# IPSv3_1.net
KiCad netlist of a schematic drawn in EAGLE
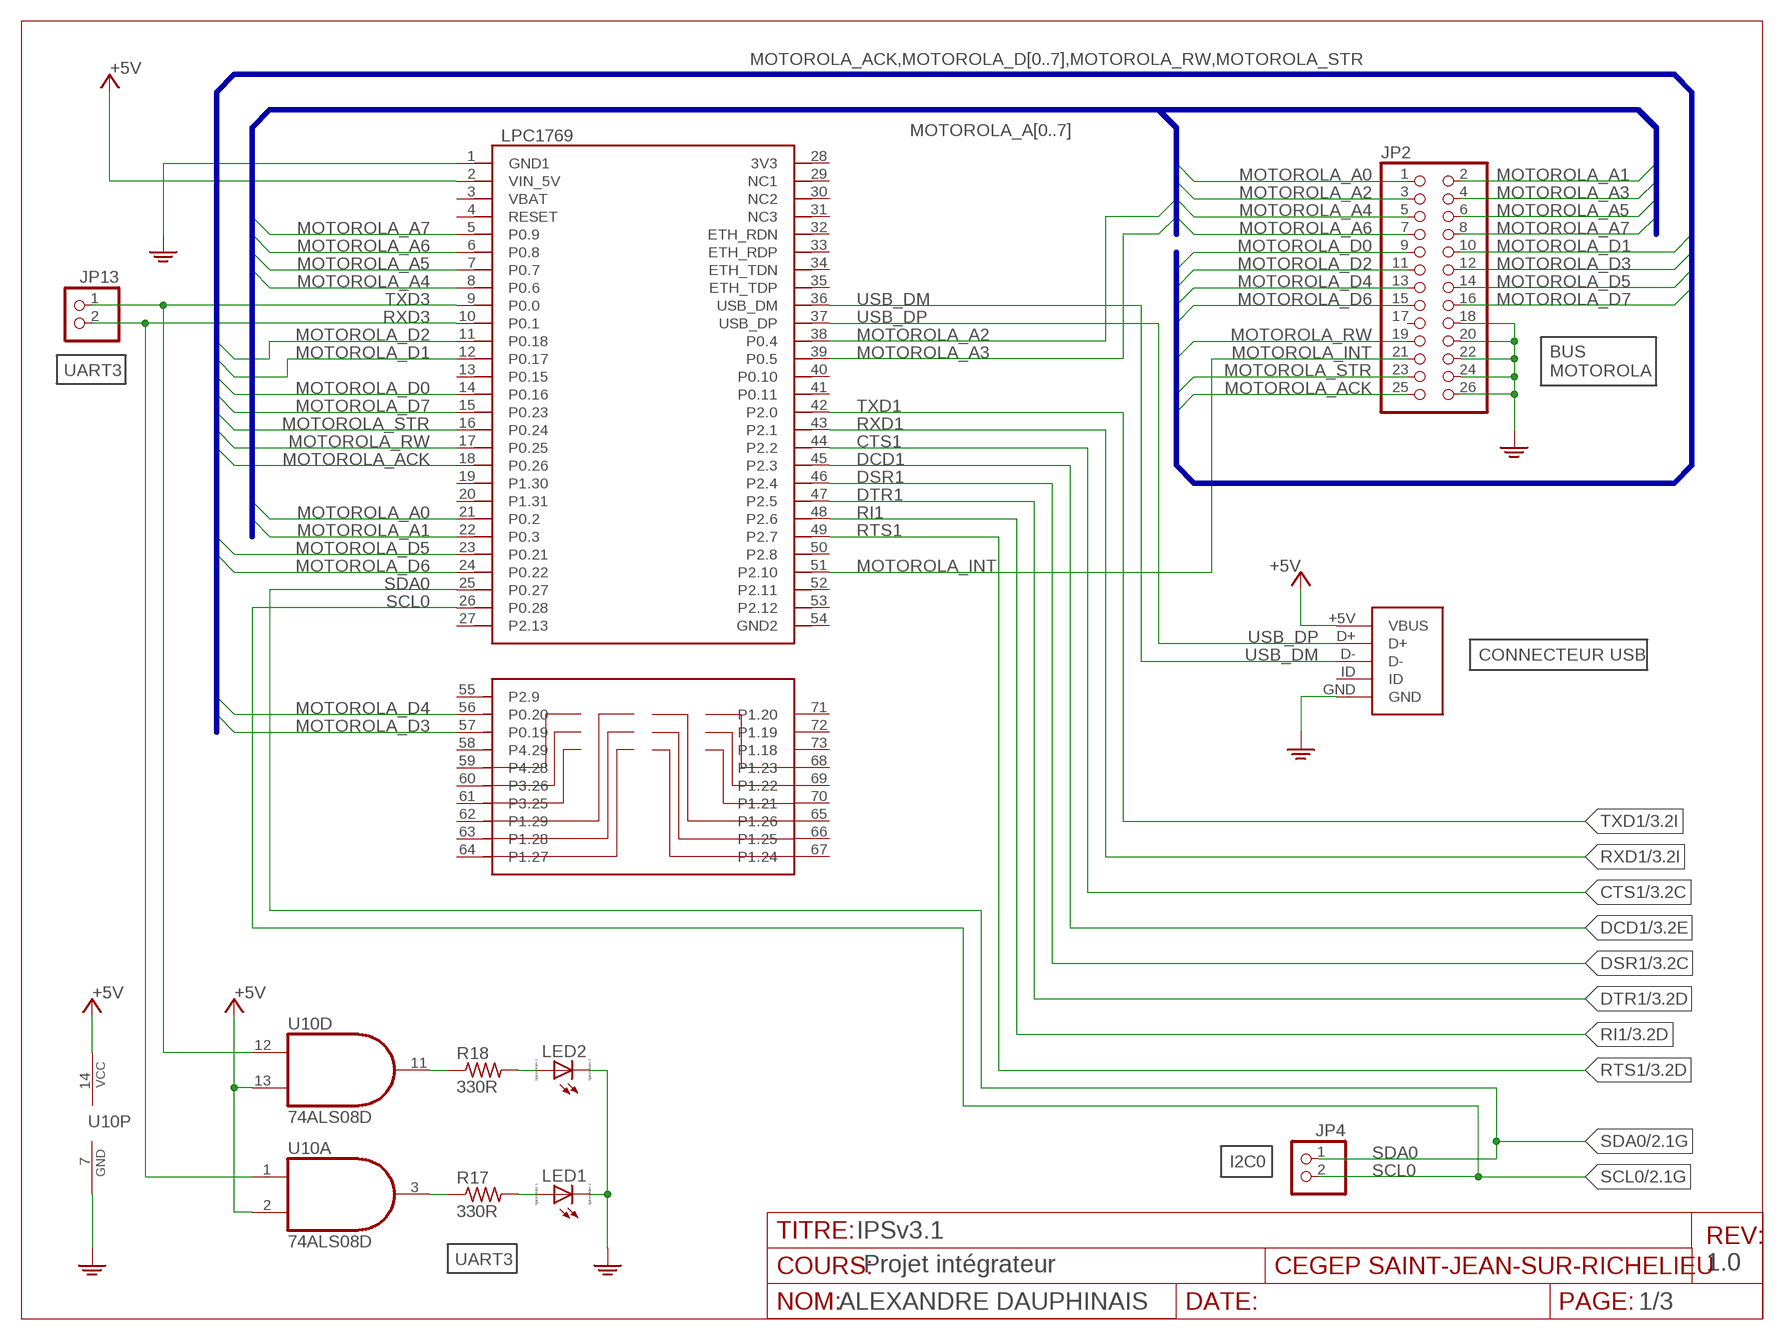
[diagram p0: schematic, sheet 1]
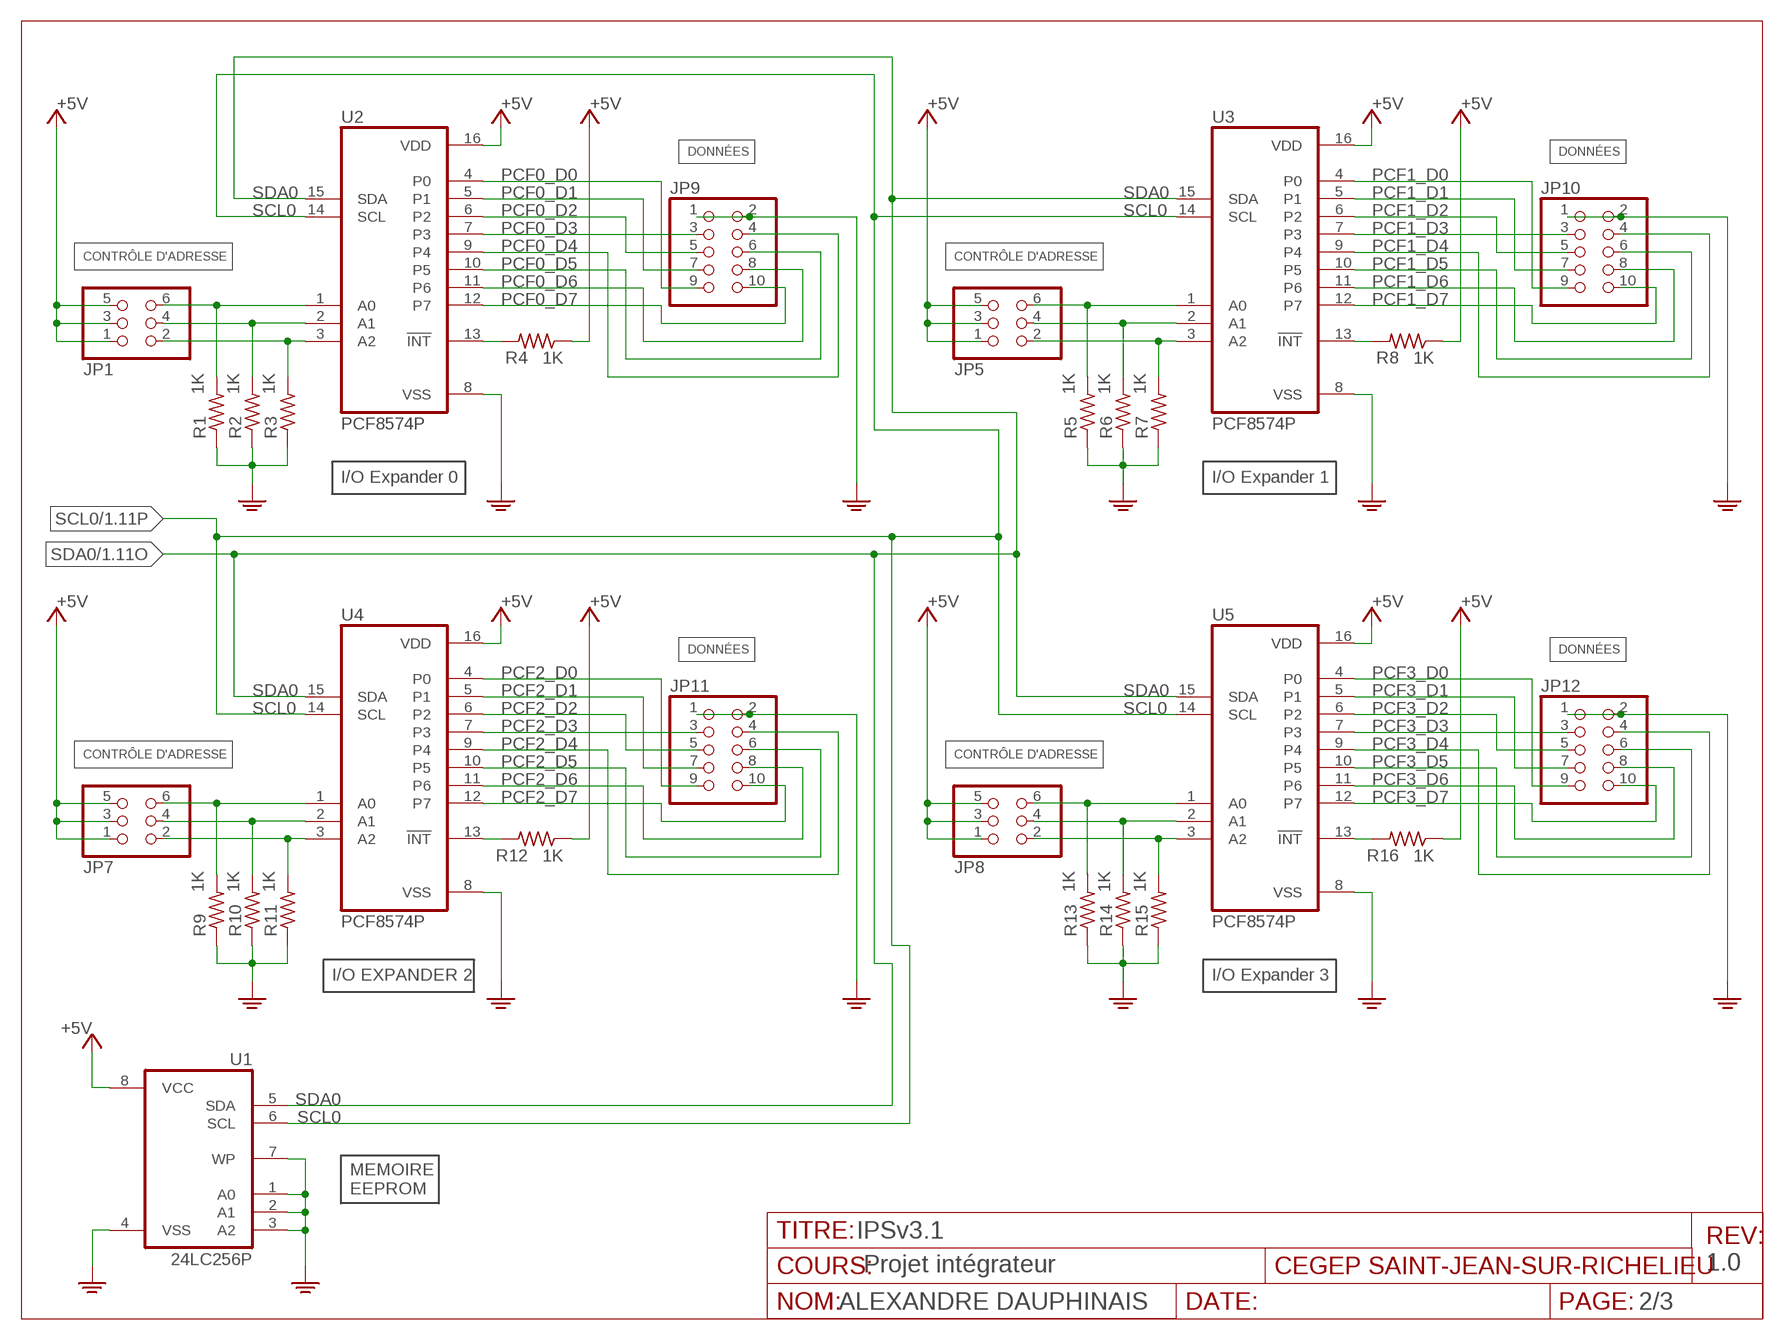
[diagram p1: schematic, sheet 2]
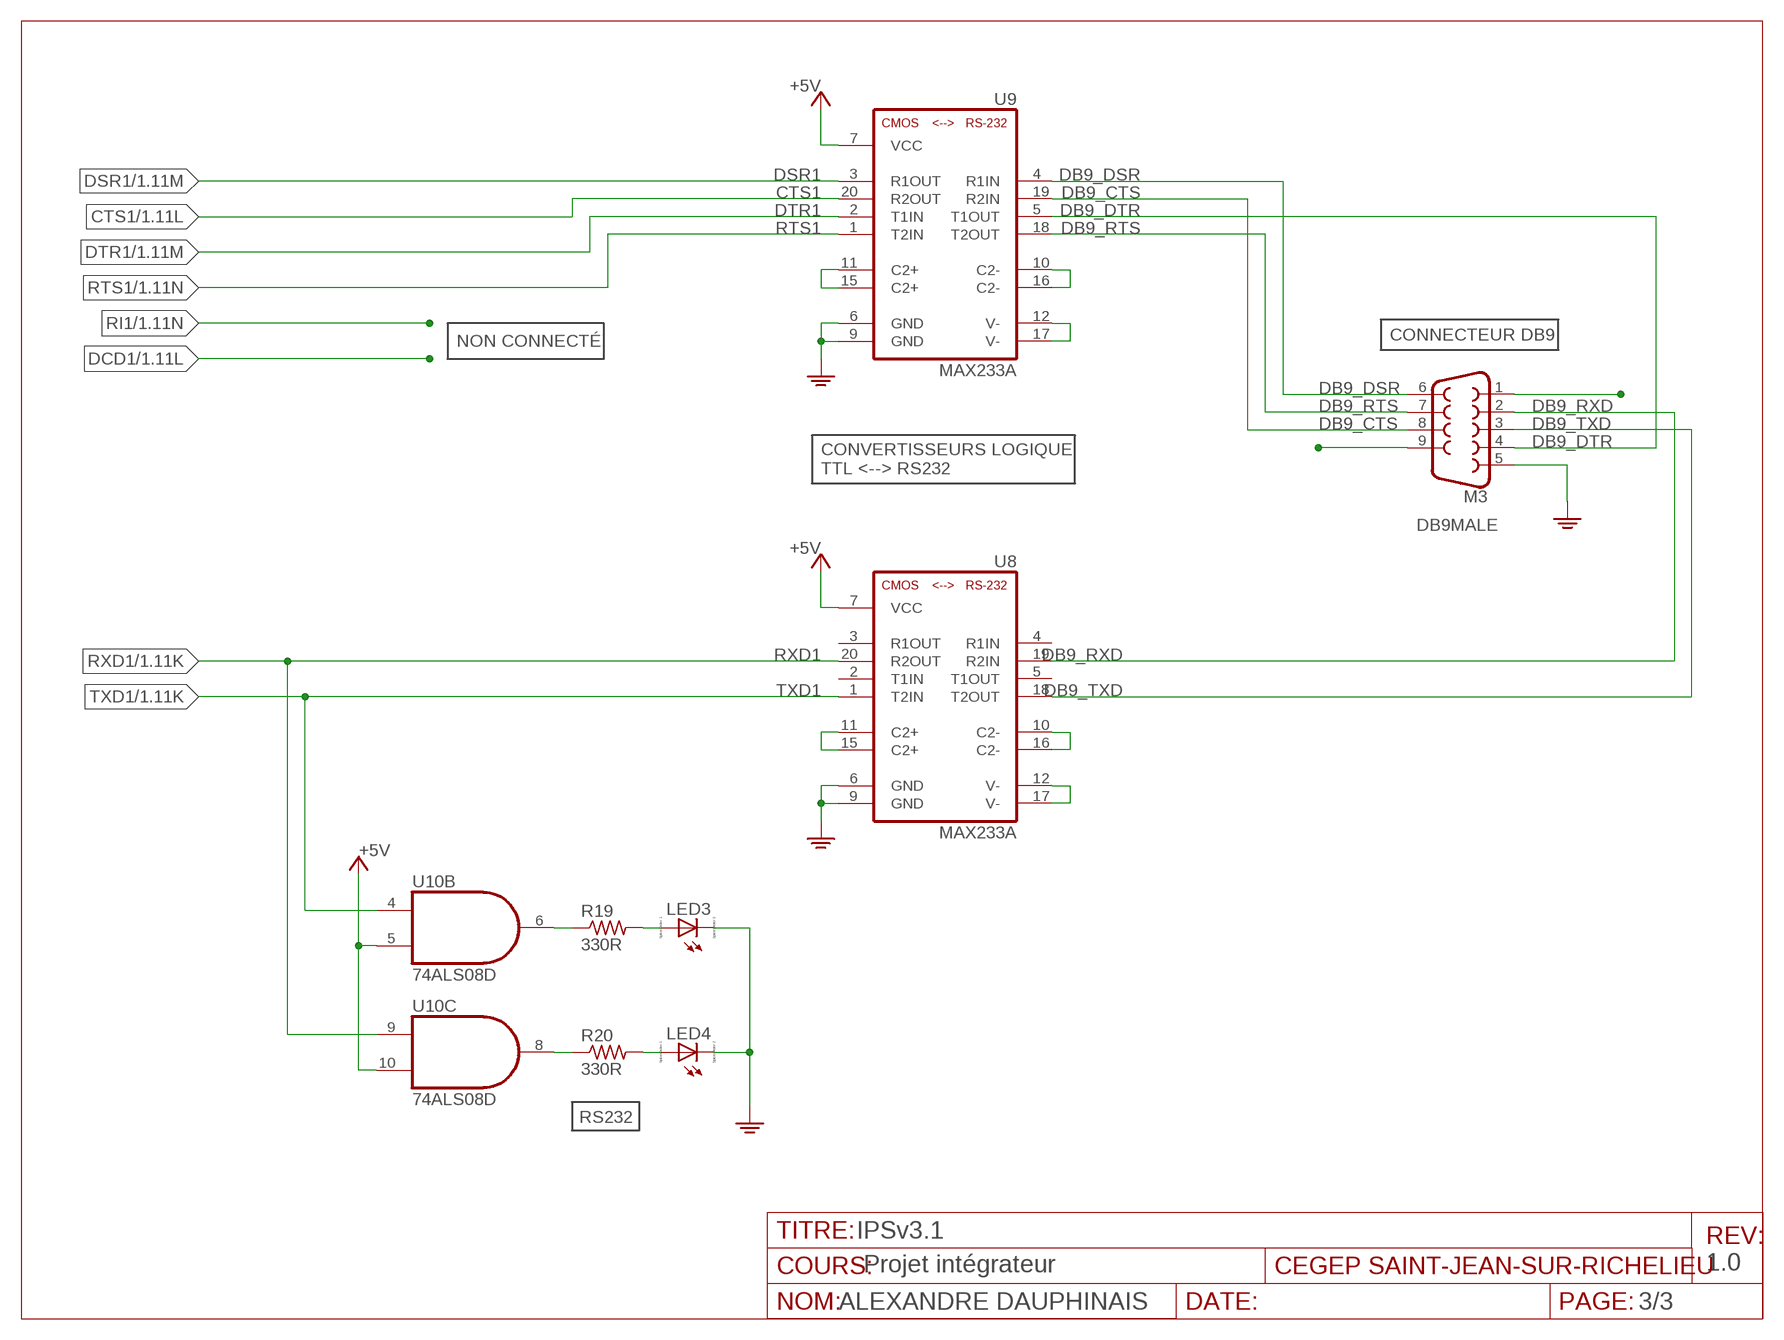
[diagram p2: schematic, sheet 3]

(export (version "E")
  (design (tool "Eeschema 10.0.6"))
  (components
    (comp (ref "LED3")
      (value "LED_JAUNE")
      (footprint "eagle-import:LED_1206")
      (libsource (lib "eagle-import") (part "LED_E"))
    )
    (comp (ref "LED4")
      (value "LED_BLEU")
      (footprint "eagle-import:LED_1206")
      (libsource (lib "eagle-import") (part "LED_E"))
    )
    (comp (ref "M3")
      (value "DB9MALE")
      (footprint "eagle-import:DB9")
      (libsource (lib "eagle-import") (part "DB9FEMALE"))
    )
    (comp (ref "R19")
      (value "330R")
      (footprint "eagle-import:R1206")
      (libsource (lib "eagle-import") (part "R-US_R1206"))
    )
    (comp (ref "R20")
      (value "330R")
      (footprint "eagle-import:R1206")
      (libsource (lib "eagle-import") (part "R-US_R1206"))
    )
    (comp (ref "U8")
      (value "MAX233A")
      (footprint "eagle-import:DIL20")
      (libsource (lib "eagle-import") (part "MAX233ACPP"))
    )
    (comp (ref "U9")
      (value "MAX233A")
      (footprint "eagle-import:DIL20")
      (libsource (lib "eagle-import") (part "MAX233ACPP"))
    )
    (comp (ref "U10")
      (value "74ALS08D")
      (footprint "eagle-import:SO14")
      (libsource (lib "eagle-import") (part "7408DALS"))
    )
    (comp (ref "JP2")
      (value "PINHD-02X13M")
      (footprint "eagle-import:02X13M")
      (libsource (lib "eagle-import") (part "PINHD-02X13M"))
    )
    (comp (ref "JP4")
      (value "PINHD-01X02M")
      (footprint "eagle-import:01X02M")
      (libsource (lib "eagle-import") (part "PINHD-01X02M"))
    )
    (comp (ref "JP13")
      (value "PINHD-01X02M")
      (footprint "eagle-import:01X02M")
      (libsource (lib "eagle-import") (part "PINHD-01X02M"))
    )
    (comp (ref "LED1")
      (value "LED_BLEU")
      (footprint "eagle-import:LED_1206")
      (libsource (lib "eagle-import") (part "LED_E"))
    )
    (comp (ref "LED2")
      (value "LED_JAUNE")
      (footprint "eagle-import:LED_1206")
      (libsource (lib "eagle-import") (part "LED_E"))
    )
    (comp (ref "M1")
      (value "LPC_LPC1769")
      (footprint "eagle-import:LPC_LPC1769")
      (libsource (lib "eagle-import") (part "LPC_LPC1769"))
    )
    (comp (ref "M2")
      (value "USB-MICRO-BREAKOUT")
      (footprint "eagle-import:USB-MICRO-BREAKOUT")
      (libsource (lib "eagle-import") (part "USB-MICRO-BREAKOUT"))
    )
    (comp (ref "R17")
      (value "330R")
      (footprint "eagle-import:R1206")
      (libsource (lib "eagle-import") (part "R-US_R1206"))
    )
    (comp (ref "R18")
      (value "330R")
      (footprint "eagle-import:R1206")
      (libsource (lib "eagle-import") (part "R-US_R1206"))
    )
    (comp (ref "JP1")
      (value "PINHD-02X03M")
      (footprint "eagle-import:02X03M")
      (libsource (lib "eagle-import") (part "PINHD-02X03M"))
    )
    (comp (ref "JP5")
      (value "PINHD-02X03M")
      (footprint "eagle-import:02X03M")
      (libsource (lib "eagle-import") (part "PINHD-02X03M"))
    )
    (comp (ref "JP7")
      (value "PINHD-02X03M")
      (footprint "eagle-import:02X03M")
      (libsource (lib "eagle-import") (part "PINHD-02X03M"))
    )
    (comp (ref "JP8")
      (value "PINHD-02X03M")
      (footprint "eagle-import:02X03M")
      (libsource (lib "eagle-import") (part "PINHD-02X03M"))
    )
    (comp (ref "JP9")
      (value "PINHD-02X05M")
      (footprint "eagle-import:02X05M")
      (libsource (lib "eagle-import") (part "PINHD-02X05M"))
    )
    (comp (ref "JP10")
      (value "PINHD-02X05M")
      (footprint "eagle-import:02X05M")
      (libsource (lib "eagle-import") (part "PINHD-02X05M"))
    )
    (comp (ref "JP11")
      (value "PINHD-02X05M")
      (footprint "eagle-import:02X05M")
      (libsource (lib "eagle-import") (part "PINHD-02X05M"))
    )
    (comp (ref "JP12")
      (value "PINHD-02X05M")
      (footprint "eagle-import:02X05M")
      (libsource (lib "eagle-import") (part "PINHD-02X05M"))
    )
    (comp (ref "R1")
      (value "1K")
      (footprint "eagle-import:R1206")
      (libsource (lib "eagle-import") (part "R-US_R1206"))
    )
    (comp (ref "R2")
      (value "1K")
      (footprint "eagle-import:R1206")
      (libsource (lib "eagle-import") (part "R-US_R1206"))
    )
    (comp (ref "R3")
      (value "1K")
      (footprint "eagle-import:R1206")
      (libsource (lib "eagle-import") (part "R-US_R1206"))
    )
    (comp (ref "R4")
      (value "1K")
      (footprint "eagle-import:R1206")
      (libsource (lib "eagle-import") (part "R-US_R1206"))
    )
    (comp (ref "R5")
      (value "1K")
      (footprint "eagle-import:R1206")
      (libsource (lib "eagle-import") (part "R-US_R1206"))
    )
    (comp (ref "R6")
      (value "1K")
      (footprint "eagle-import:R1206")
      (libsource (lib "eagle-import") (part "R-US_R1206"))
    )
    (comp (ref "R7")
      (value "1K")
      (footprint "eagle-import:R1206")
      (libsource (lib "eagle-import") (part "R-US_R1206"))
    )
    (comp (ref "R8")
      (value "1K")
      (footprint "eagle-import:R1206")
      (libsource (lib "eagle-import") (part "R-US_R1206"))
    )
    (comp (ref "R9")
      (value "1K")
      (footprint "eagle-import:R1206")
      (libsource (lib "eagle-import") (part "R-US_R1206"))
    )
    (comp (ref "R10")
      (value "1K")
      (footprint "eagle-import:R1206")
      (libsource (lib "eagle-import") (part "R-US_R1206"))
    )
    (comp (ref "R11")
      (value "1K")
      (footprint "eagle-import:R1206")
      (libsource (lib "eagle-import") (part "R-US_R1206"))
    )
    (comp (ref "R12")
      (value "1K")
      (footprint "eagle-import:R1206")
      (libsource (lib "eagle-import") (part "R-US_R1206"))
    )
    (comp (ref "R13")
      (value "1K")
      (footprint "eagle-import:R1206")
      (libsource (lib "eagle-import") (part "R-US_R1206"))
    )
    (comp (ref "R14")
      (value "1K")
      (footprint "eagle-import:R1206")
      (libsource (lib "eagle-import") (part "R-US_R1206"))
    )
    (comp (ref "R15")
      (value "1K")
      (footprint "eagle-import:R1206")
      (libsource (lib "eagle-import") (part "R-US_R1206"))
    )
    (comp (ref "R16")
      (value "1K")
      (footprint "eagle-import:R1206")
      (libsource (lib "eagle-import") (part "R-US_R1206"))
    )
    (comp (ref "U1")
      (value "24LC256P")
      (footprint "eagle-import:DIL08")
      (libsource (lib "eagle-import") (part "24LC256P"))
    )
    (comp (ref "U2")
      (value "PCF8574P")
      (footprint "eagle-import:DIL16")
      (libsource (lib "eagle-import") (part "PCF8574P"))
    )
    (comp (ref "U3")
      (value "PCF8574P")
      (footprint "eagle-import:DIL16")
      (libsource (lib "eagle-import") (part "PCF8574P"))
    )
    (comp (ref "U4")
      (value "PCF8574P")
      (footprint "eagle-import:DIL16")
      (libsource (lib "eagle-import") (part "PCF8574P"))
    )
    (comp (ref "U5")
      (value "PCF8574P")
      (footprint "eagle-import:DIL16")
      (libsource (lib "eagle-import") (part "PCF8574P"))
    )
  )
  (nets
    (net (code "1") (name "+5V") (class "Default")
      (node (ref "JP1") (pin "1") (pinfunction "1_1") (pintype "passive"))
      (node (ref "JP1") (pin "3") (pinfunction "3_3") (pintype "passive"))
      (node (ref "JP1") (pin "5") (pinfunction "5_5") (pintype "passive"))
      (node (ref "JP5") (pin "1") (pinfunction "1_1") (pintype "passive"))
      (node (ref "JP5") (pin "3") (pinfunction "3_3") (pintype "passive"))
      (node (ref "JP5") (pin "5") (pinfunction "5_5") (pintype "passive"))
      (node (ref "JP7") (pin "1") (pinfunction "1_1") (pintype "passive"))
      (node (ref "JP7") (pin "3") (pinfunction "3_3") (pintype "passive"))
      (node (ref "JP7") (pin "5") (pinfunction "5_5") (pintype "passive"))
      (node (ref "JP8") (pin "1") (pinfunction "1_1") (pintype "passive"))
      (node (ref "JP8") (pin "3") (pinfunction "3_3") (pintype "passive"))
      (node (ref "JP8") (pin "5") (pinfunction "5_5") (pintype "passive"))
      (node (ref "M1") (pin "2") (pinfunction "VIN_5V_2") (pintype "bidirectional"))
      (node (ref "M2") (pin "+5V") (pinfunction "VBUS_+5V") (pintype "power_in"))
      (node (ref "R12") (pin "1") (pinfunction "1_1") (pintype "passive"))
      (node (ref "R16") (pin "1") (pinfunction "1_1") (pintype "passive"))
      (node (ref "R4") (pin "1") (pinfunction "1_1") (pintype "passive"))
      (node (ref "R8") (pin "1") (pinfunction "1_1") (pintype "passive"))
      (node (ref "U1") (pin "8") (pinfunction "VCC_8") (pintype "power_in"))
      (node (ref "U10") (pin "10") (pinfunction "I1_10") (pintype "input"))
      (node (ref "U10") (pin "13") (pinfunction "I1_13") (pintype "input"))
      (node (ref "U10") (pin "14") (pinfunction "VCC_14") (pintype "power_in"))
      (node (ref "U10") (pin "2") (pinfunction "I1_2") (pintype "input"))
      (node (ref "U10") (pin "5") (pinfunction "I1_5") (pintype "input"))
      (node (ref "U2") (pin "16") (pinfunction "VDD_16") (pintype "power_in"))
      (node (ref "U3") (pin "16") (pinfunction "VDD_16") (pintype "power_in"))
      (node (ref "U4") (pin "16") (pinfunction "VDD_16") (pintype "power_in"))
      (node (ref "U5") (pin "16") (pinfunction "VDD_16") (pintype "power_in"))
      (node (ref "U8") (pin "7") (pinfunction "VCC_7") (pintype "power_in"))
      (node (ref "U9") (pin "7") (pinfunction "VCC_7") (pintype "power_in"))
    )
    (net (code "4") (name "CTS1") (class "Default")
      (node (ref "M1") (pin "44") (pinfunction "P2.2_44") (pintype "bidirectional"))
      (node (ref "U9") (pin "20") (pinfunction "R2OUT_20") (pintype "output"))
    )
    (net (code "5") (name "DB9_CTS") (class "Default")
      (node (ref "M3") (pin "8") (pinfunction "8_8") (pintype "passive"))
      (node (ref "U9") (pin "19") (pinfunction "R2IN_19") (pintype "input"))
    )
    (net (code "6") (name "DB9_DSR") (class "Default")
      (node (ref "M3") (pin "6") (pinfunction "6_6") (pintype "passive"))
      (node (ref "U9") (pin "4") (pinfunction "R1IN_4") (pintype "input"))
    )
    (net (code "7") (name "DB9_DTR") (class "Default")
      (node (ref "M3") (pin "4") (pinfunction "4_4") (pintype "passive"))
      (node (ref "U9") (pin "5") (pinfunction "T1OUT_5") (pintype "output"))
    )
    (net (code "8") (name "DB9_RTS") (class "Default")
      (node (ref "M3") (pin "7") (pinfunction "7_7") (pintype "passive"))
      (node (ref "U9") (pin "18") (pinfunction "T2OUT_18") (pintype "output"))
    )
    (net (code "9") (name "DB9_RXD") (class "Default")
      (node (ref "M3") (pin "2") (pinfunction "2_2") (pintype "passive"))
      (node (ref "U8") (pin "19") (pinfunction "R2IN_19") (pintype "input"))
    )
    (net (code "10") (name "DB9_TXD") (class "Default")
      (node (ref "M3") (pin "3") (pinfunction "3_3") (pintype "passive"))
      (node (ref "U8") (pin "18") (pinfunction "T2OUT_18") (pintype "output"))
    )
    (net (code "11") (name "DCD1") (class "Default")
      (node (ref "M1") (pin "45") (pinfunction "P2.3_45") (pintype "bidirectional"))
    )
    (net (code "12") (name "DSR1") (class "Default")
      (node (ref "M1") (pin "46") (pinfunction "P2.4_46") (pintype "bidirectional"))
      (node (ref "U9") (pin "3") (pinfunction "R1OUT_3") (pintype "output"))
    )
    (net (code "13") (name "DTR1") (class "Default")
      (node (ref "M1") (pin "47") (pinfunction "P2.5_47") (pintype "bidirectional"))
      (node (ref "U9") (pin "2") (pinfunction "T1IN_2") (pintype "input"))
    )
    (net (code "14") (name "GND") (class "Default")
      (node (ref "JP10") (pin "1") (pinfunction "1_1") (pintype "passive"))
      (node (ref "JP10") (pin "2") (pinfunction "2_2") (pintype "passive"))
      (node (ref "JP11") (pin "1") (pinfunction "1_1") (pintype "passive"))
      (node (ref "JP11") (pin "2") (pinfunction "2_2") (pintype "passive"))
      (node (ref "JP12") (pin "1") (pinfunction "1_1") (pintype "passive"))
      (node (ref "JP12") (pin "2") (pinfunction "2_2") (pintype "passive"))
      (node (ref "JP2") (pin "18") (pinfunction "18_18") (pintype "passive"))
      (node (ref "JP2") (pin "20") (pinfunction "20_20") (pintype "passive"))
      (node (ref "JP2") (pin "22") (pinfunction "22_22") (pintype "passive"))
      (node (ref "JP2") (pin "24") (pinfunction "24_24") (pintype "passive"))
      (node (ref "JP2") (pin "26") (pinfunction "26_26") (pintype "passive"))
      (node (ref "JP9") (pin "1") (pinfunction "1_1") (pintype "passive"))
      (node (ref "JP9") (pin "2") (pinfunction "2_2") (pintype "passive"))
      (node (ref "LED1") (pin "C") (pinfunction "C_C") (pintype "passive"))
      (node (ref "LED2") (pin "C") (pinfunction "C_C") (pintype "passive"))
      (node (ref "LED3") (pin "C") (pinfunction "C_C") (pintype "passive"))
      (node (ref "LED4") (pin "C") (pinfunction "C_C") (pintype "passive"))
      (node (ref "M1") (pin "1") (pinfunction "GND1_1") (pintype "bidirectional"))
      (node (ref "M2") (pin "GND") (pinfunction "GND_GND") (pintype "power_in"))
      (node (ref "M3") (pin "5") (pinfunction "5_5") (pintype "passive"))
      (node (ref "R1") (pin "1") (pinfunction "1_1") (pintype "passive"))
      (node (ref "R10") (pin "1") (pinfunction "1_1") (pintype "passive"))
      (node (ref "R11") (pin "1") (pinfunction "1_1") (pintype "passive"))
      (node (ref "R13") (pin "1") (pinfunction "1_1") (pintype "passive"))
      (node (ref "R14") (pin "1") (pinfunction "1_1") (pintype "passive"))
      (node (ref "R15") (pin "1") (pinfunction "1_1") (pintype "passive"))
      (node (ref "R2") (pin "1") (pinfunction "1_1") (pintype "passive"))
      (node (ref "R3") (pin "1") (pinfunction "1_1") (pintype "passive"))
      (node (ref "R5") (pin "1") (pinfunction "1_1") (pintype "passive"))
      (node (ref "R6") (pin "1") (pinfunction "1_1") (pintype "passive"))
      (node (ref "R7") (pin "1") (pinfunction "1_1") (pintype "passive"))
      (node (ref "R9") (pin "1") (pinfunction "1_1") (pintype "passive"))
      (node (ref "U1") (pin "1") (pinfunction "A0_1") (pintype "input"))
      (node (ref "U1") (pin "2") (pinfunction "A1_2") (pintype "input"))
      (node (ref "U1") (pin "3") (pinfunction "A2_3") (pintype "input"))
      (node (ref "U1") (pin "4") (pinfunction "VSS_4") (pintype "power_in"))
      (node (ref "U1") (pin "7") (pinfunction "WP_7") (pintype "input"))
      (node (ref "U10") (pin "7") (pinfunction "GND_7") (pintype "power_in"))
      (node (ref "U2") (pin "8") (pinfunction "VSS_8") (pintype "power_in"))
      (node (ref "U3") (pin "8") (pinfunction "VSS_8") (pintype "power_in"))
      (node (ref "U4") (pin "8") (pinfunction "VSS_8") (pintype "power_in"))
      (node (ref "U5") (pin "8") (pinfunction "VSS_8") (pintype "power_in"))
      (node (ref "U8") (pin "6") (pinfunction "GND_6") (pintype "power_in"))
      (node (ref "U8") (pin "9") (pinfunction "GND_9") (pintype "power_in"))
      (node (ref "U9") (pin "6") (pinfunction "GND_6") (pintype "power_in"))
      (node (ref "U9") (pin "9") (pinfunction "GND_9") (pintype "power_in"))
    )
    (net (code "15") (name "MOTOROLA_A0") (class "Default")
      (node (ref "JP2") (pin "1") (pinfunction "1_1") (pintype "passive"))
      (node (ref "M1") (pin "21") (pinfunction "P0.2_21") (pintype "bidirectional"))
    )
    (net (code "16") (name "MOTOROLA_A1") (class "Default")
      (node (ref "JP2") (pin "2") (pinfunction "2_2") (pintype "passive"))
      (node (ref "M1") (pin "22") (pinfunction "P0.3_22") (pintype "bidirectional"))
    )
    (net (code "17") (name "MOTOROLA_A2") (class "Default")
      (node (ref "JP2") (pin "3") (pinfunction "3_3") (pintype "passive"))
      (node (ref "M1") (pin "38") (pinfunction "P0.4_38") (pintype "bidirectional"))
    )
    (net (code "18") (name "MOTOROLA_A3") (class "Default")
      (node (ref "JP2") (pin "4") (pinfunction "4_4") (pintype "passive"))
      (node (ref "M1") (pin "39") (pinfunction "P0.5_39") (pintype "bidirectional"))
    )
    (net (code "19") (name "MOTOROLA_A4") (class "Default")
      (node (ref "JP2") (pin "5") (pinfunction "5_5") (pintype "passive"))
      (node (ref "M1") (pin "8") (pinfunction "P0.6_8") (pintype "bidirectional"))
    )
    (net (code "20") (name "MOTOROLA_A5") (class "Default")
      (node (ref "JP2") (pin "6") (pinfunction "6_6") (pintype "passive"))
      (node (ref "M1") (pin "7") (pinfunction "P0.7_7") (pintype "bidirectional"))
    )
    (net (code "21") (name "MOTOROLA_A6") (class "Default")
      (node (ref "JP2") (pin "7") (pinfunction "7_7") (pintype "passive"))
      (node (ref "M1") (pin "6") (pinfunction "P0.8_6") (pintype "bidirectional"))
    )
    (net (code "22") (name "MOTOROLA_A7") (class "Default")
      (node (ref "JP2") (pin "8") (pinfunction "8_8") (pintype "passive"))
      (node (ref "M1") (pin "5") (pinfunction "P0.9_5") (pintype "bidirectional"))
    )
    (net (code "23") (name "MOTOROLA_ACK") (class "Default")
      (node (ref "JP2") (pin "25") (pinfunction "25_25") (pintype "passive"))
      (node (ref "M1") (pin "18") (pinfunction "P0.26_18") (pintype "bidirectional"))
    )
    (net (code "24") (name "MOTOROLA_D0") (class "Default")
      (node (ref "JP2") (pin "9") (pinfunction "9_9") (pintype "passive"))
      (node (ref "M1") (pin "14") (pinfunction "P0.16_14") (pintype "bidirectional"))
    )
    (net (code "25") (name "MOTOROLA_D1") (class "Default")
      (node (ref "JP2") (pin "10") (pinfunction "10_10") (pintype "passive"))
      (node (ref "M1") (pin "12") (pinfunction "P0.17_12") (pintype "bidirectional"))
    )
    (net (code "26") (name "MOTOROLA_D2") (class "Default")
      (node (ref "JP2") (pin "11") (pinfunction "11_11") (pintype "passive"))
      (node (ref "M1") (pin "11") (pinfunction "P0.18_11") (pintype "bidirectional"))
    )
    (net (code "27") (name "MOTOROLA_D3") (class "Default")
      (node (ref "JP2") (pin "12") (pinfunction "12_12") (pintype "passive"))
      (node (ref "M1") (pin "57") (pinfunction "P0.19_57") (pintype "bidirectional"))
    )
    (net (code "28") (name "MOTOROLA_D4") (class "Default")
      (node (ref "JP2") (pin "13") (pinfunction "13_13") (pintype "passive"))
      (node (ref "M1") (pin "56") (pinfunction "P0.20_56") (pintype "bidirectional"))
    )
    (net (code "29") (name "MOTOROLA_D5") (class "Default")
      (node (ref "JP2") (pin "14") (pinfunction "14_14") (pintype "passive"))
      (node (ref "M1") (pin "23") (pinfunction "P0.21_23") (pintype "bidirectional"))
    )
    (net (code "30") (name "MOTOROLA_D6") (class "Default")
      (node (ref "JP2") (pin "15") (pinfunction "15_15") (pintype "passive"))
      (node (ref "M1") (pin "24") (pinfunction "P0.22_24") (pintype "bidirectional"))
    )
    (net (code "31") (name "MOTOROLA_D7") (class "Default")
      (node (ref "JP2") (pin "16") (pinfunction "16_16") (pintype "passive"))
      (node (ref "M1") (pin "15") (pinfunction "P0.23_15") (pintype "bidirectional"))
    )
    (net (code "32") (name "MOTOROLA_INT") (class "Default")
      (node (ref "JP2") (pin "21") (pinfunction "21_21") (pintype "passive"))
      (node (ref "M1") (pin "51") (pinfunction "P2.10_51") (pintype "bidirectional"))
    )
    (net (code "33") (name "MOTOROLA_RW") (class "Default")
      (node (ref "JP2") (pin "19") (pinfunction "19_19") (pintype "passive"))
      (node (ref "M1") (pin "17") (pinfunction "P0.25_17") (pintype "bidirectional"))
    )
    (net (code "34") (name "MOTOROLA_STR") (class "Default")
      (node (ref "JP2") (pin "23") (pinfunction "23_23") (pintype "passive"))
      (node (ref "M1") (pin "16") (pinfunction "P0.24_16") (pintype "bidirectional"))
    )
    (net (code "35") (name "Net-(LED1-PadA)") (class "Default")
      (node (ref "LED1") (pin "A") (pinfunction "A_A") (pintype "passive"))
      (node (ref "R17") (pin "2") (pinfunction "2_2") (pintype "passive"))
    )
    (net (code "36") (name "Net-(LED2-PadA)") (class "Default")
      (node (ref "LED2") (pin "A") (pinfunction "A_A") (pintype "passive"))
      (node (ref "R18") (pin "2") (pinfunction "2_2") (pintype "passive"))
    )
    (net (code "37") (name "Net-(LED3-PadA)") (class "Default")
      (node (ref "LED3") (pin "A") (pinfunction "A_A") (pintype "passive"))
      (node (ref "R19") (pin "2") (pinfunction "2_2") (pintype "passive"))
    )
    (net (code "38") (name "Net-(LED4-PadA)") (class "Default")
      (node (ref "LED4") (pin "A") (pinfunction "A_A") (pintype "passive"))
      (node (ref "R20") (pin "2") (pinfunction "2_2") (pintype "passive"))
    )
    (net (code "39") (name "Net-(U2-A0)") (class "Default")
      (node (ref "JP1") (pin "6") (pinfunction "6_6") (pintype "passive"))
      (node (ref "R1") (pin "2") (pinfunction "2_2") (pintype "passive"))
      (node (ref "U2") (pin "1") (pinfunction "A0_1") (pintype "input"))
    )
    (net (code "40") (name "Net-(U2-A1)") (class "Default")
      (node (ref "JP1") (pin "4") (pinfunction "4_4") (pintype "passive"))
      (node (ref "R2") (pin "2") (pinfunction "2_2") (pintype "passive"))
      (node (ref "U2") (pin "2") (pinfunction "A1_2") (pintype "input"))
    )
    (net (code "41") (name "Net-(U2-A2)") (class "Default")
      (node (ref "JP1") (pin "2") (pinfunction "2_2") (pintype "passive"))
      (node (ref "R3") (pin "2") (pinfunction "2_2") (pintype "passive"))
      (node (ref "U2") (pin "3") (pinfunction "A2_3") (pintype "input"))
    )
    (net (code "42") (name "Net-(U2-~{INT})") (class "Default")
      (node (ref "R4") (pin "2") (pinfunction "2_2") (pintype "passive"))
      (node (ref "U2") (pin "13") (pinfunction "~{INT}_13") (pintype "output"))
    )
    (net (code "43") (name "Net-(U3-A0)") (class "Default")
      (node (ref "JP5") (pin "6") (pinfunction "6_6") (pintype "passive"))
      (node (ref "R5") (pin "2") (pinfunction "2_2") (pintype "passive"))
      (node (ref "U3") (pin "1") (pinfunction "A0_1") (pintype "input"))
    )
    (net (code "44") (name "Net-(U3-A1)") (class "Default")
      (node (ref "JP5") (pin "4") (pinfunction "4_4") (pintype "passive"))
      (node (ref "R6") (pin "2") (pinfunction "2_2") (pintype "passive"))
      (node (ref "U3") (pin "2") (pinfunction "A1_2") (pintype "input"))
    )
    (net (code "45") (name "Net-(U3-A2)") (class "Default")
      (node (ref "JP5") (pin "2") (pinfunction "2_2") (pintype "passive"))
      (node (ref "R7") (pin "2") (pinfunction "2_2") (pintype "passive"))
      (node (ref "U3") (pin "3") (pinfunction "A2_3") (pintype "input"))
    )
    (net (code "46") (name "Net-(U3-~{INT})") (class "Default")
      (node (ref "R8") (pin "2") (pinfunction "2_2") (pintype "passive"))
      (node (ref "U3") (pin "13") (pinfunction "~{INT}_13") (pintype "output"))
    )
    (net (code "47") (name "Net-(U4-A0)") (class "Default")
      (node (ref "JP7") (pin "6") (pinfunction "6_6") (pintype "passive"))
      (node (ref "R9") (pin "2") (pinfunction "2_2") (pintype "passive"))
      (node (ref "U4") (pin "1") (pinfunction "A0_1") (pintype "input"))
    )
    (net (code "48") (name "Net-(U4-A1)") (class "Default")
      (node (ref "JP7") (pin "4") (pinfunction "4_4") (pintype "passive"))
      (node (ref "R10") (pin "2") (pinfunction "2_2") (pintype "passive"))
      (node (ref "U4") (pin "2") (pinfunction "A1_2") (pintype "input"))
    )
    (net (code "49") (name "Net-(U4-A2)") (class "Default")
      (node (ref "JP7") (pin "2") (pinfunction "2_2") (pintype "passive"))
      (node (ref "R11") (pin "2") (pinfunction "2_2") (pintype "passive"))
      (node (ref "U4") (pin "3") (pinfunction "A2_3") (pintype "input"))
    )
    (net (code "50") (name "Net-(U4-~{INT})") (class "Default")
      (node (ref "R12") (pin "2") (pinfunction "2_2") (pintype "passive"))
      (node (ref "U4") (pin "13") (pinfunction "~{INT}_13") (pintype "output"))
    )
    (net (code "51") (name "Net-(U5-A0)") (class "Default")
      (node (ref "JP8") (pin "6") (pinfunction "6_6") (pintype "passive"))
      (node (ref "R13") (pin "2") (pinfunction "2_2") (pintype "passive"))
      (node (ref "U5") (pin "1") (pinfunction "A0_1") (pintype "input"))
    )
    (net (code "52") (name "Net-(U5-A1)") (class "Default")
      (node (ref "JP8") (pin "4") (pinfunction "4_4") (pintype "passive"))
      (node (ref "R14") (pin "2") (pinfunction "2_2") (pintype "passive"))
      (node (ref "U5") (pin "2") (pinfunction "A1_2") (pintype "input"))
    )
    (net (code "53") (name "Net-(U5-A2)") (class "Default")
      (node (ref "JP8") (pin "2") (pinfunction "2_2") (pintype "passive"))
      (node (ref "R15") (pin "2") (pinfunction "2_2") (pintype "passive"))
      (node (ref "U5") (pin "3") (pinfunction "A2_3") (pintype "input"))
    )
    (net (code "54") (name "Net-(U5-~{INT})") (class "Default")
      (node (ref "R16") (pin "2") (pinfunction "2_2") (pintype "passive"))
      (node (ref "U5") (pin "13") (pinfunction "~{INT}_13") (pintype "output"))
    )
    (net (code "55") (name "Net-(U8-C2+-Pad11)") (class "Default")
      (node (ref "U8") (pin "11") (pinfunction "C2+_11") (pintype "passive"))
      (node (ref "U8") (pin "15") (pinfunction "C2+_15") (pintype "passive"))
    )
    (net (code "56") (name "Net-(U8-C2--Pad10)") (class "Default")
      (node (ref "U8") (pin "10") (pinfunction "C2-_10") (pintype "passive"))
      (node (ref "U8") (pin "16") (pinfunction "C2-_16") (pintype "passive"))
    )
    (net (code "57") (name "Net-(U8-V--Pad12)") (class "Default")
      (node (ref "U8") (pin "12") (pinfunction "V-_12") (pintype "passive"))
      (node (ref "U8") (pin "17") (pinfunction "V-_17") (pintype "passive"))
    )
    (net (code "58") (name "Net-(U9-C2+-Pad11)") (class "Default")
      (node (ref "U9") (pin "11") (pinfunction "C2+_11") (pintype "passive"))
      (node (ref "U9") (pin "15") (pinfunction "C2+_15") (pintype "passive"))
    )
    (net (code "59") (name "Net-(U9-C2--Pad10)") (class "Default")
      (node (ref "U9") (pin "10") (pinfunction "C2-_10") (pintype "passive"))
      (node (ref "U9") (pin "16") (pinfunction "C2-_16") (pintype "passive"))
    )
    (net (code "60") (name "Net-(U9-V--Pad12)") (class "Default")
      (node (ref "U9") (pin "12") (pinfunction "V-_12") (pintype "passive"))
      (node (ref "U9") (pin "17") (pinfunction "V-_17") (pintype "passive"))
    )
    (net (code "61") (name "Net-(U10A-O)") (class "Default")
      (node (ref "R17") (pin "1") (pinfunction "1_1") (pintype "passive"))
      (node (ref "U10") (pin "3") (pinfunction "O_3") (pintype "output"))
    )
    (net (code "62") (name "Net-(U10B-O)") (class "Default")
      (node (ref "R19") (pin "1") (pinfunction "1_1") (pintype "passive"))
      (node (ref "U10") (pin "6") (pinfunction "O_6") (pintype "output"))
    )
    (net (code "63") (name "Net-(U10C-O)") (class "Default")
      (node (ref "R20") (pin "1") (pinfunction "1_1") (pintype "passive"))
      (node (ref "U10") (pin "8") (pinfunction "O_8") (pintype "output"))
    )
    (net (code "64") (name "Net-(U10D-O)") (class "Default")
      (node (ref "R18") (pin "1") (pinfunction "1_1") (pintype "passive"))
      (node (ref "U10") (pin "11") (pinfunction "O_11") (pintype "output"))
    )
    (net (code "65") (name "PCF0_D0") (class "Default")
      (node (ref "JP9") (pin "9") (pinfunction "9_9") (pintype "passive"))
      (node (ref "U2") (pin "4") (pinfunction "P0_4") (pintype "bidirectional"))
    )
    (net (code "66") (name "PCF0_D1") (class "Default")
      (node (ref "JP9") (pin "7") (pinfunction "7_7") (pintype "passive"))
      (node (ref "U2") (pin "5") (pinfunction "P1_5") (pintype "bidirectional"))
    )
    (net (code "67") (name "PCF0_D2") (class "Default")
      (node (ref "JP9") (pin "5") (pinfunction "5_5") (pintype "passive"))
      (node (ref "U2") (pin "6") (pinfunction "P2_6") (pintype "bidirectional"))
    )
    (net (code "68") (name "PCF0_D3") (class "Default")
      (node (ref "JP9") (pin "3") (pinfunction "3_3") (pintype "passive"))
      (node (ref "U2") (pin "7") (pinfunction "P3_7") (pintype "bidirectional"))
    )
    (net (code "69") (name "PCF0_D4") (class "Default")
      (node (ref "JP9") (pin "4") (pinfunction "4_4") (pintype "passive"))
      (node (ref "U2") (pin "9") (pinfunction "P4_9") (pintype "bidirectional"))
    )
    (net (code "70") (name "PCF0_D5") (class "Default")
      (node (ref "JP9") (pin "6") (pinfunction "6_6") (pintype "passive"))
      (node (ref "U2") (pin "10") (pinfunction "P5_10") (pintype "bidirectional"))
    )
    (net (code "71") (name "PCF0_D6") (class "Default")
      (node (ref "JP9") (pin "8") (pinfunction "8_8") (pintype "passive"))
      (node (ref "U2") (pin "11") (pinfunction "P6_11") (pintype "bidirectional"))
    )
    (net (code "72") (name "PCF0_D7") (class "Default")
      (node (ref "JP9") (pin "10") (pinfunction "10_10") (pintype "passive"))
      (node (ref "U2") (pin "12") (pinfunction "P7_12") (pintype "bidirectional"))
    )
    (net (code "73") (name "PCF1_D0") (class "Default")
      (node (ref "JP10") (pin "9") (pinfunction "9_9") (pintype "passive"))
      (node (ref "U3") (pin "4") (pinfunction "P0_4") (pintype "bidirectional"))
    )
    (net (code "74") (name "PCF1_D1") (class "Default")
      (node (ref "JP10") (pin "7") (pinfunction "7_7") (pintype "passive"))
      (node (ref "U3") (pin "5") (pinfunction "P1_5") (pintype "bidirectional"))
    )
    (net (code "75") (name "PCF1_D2") (class "Default")
      (node (ref "JP10") (pin "5") (pinfunction "5_5") (pintype "passive"))
      (node (ref "U3") (pin "6") (pinfunction "P2_6") (pintype "bidirectional"))
    )
    (net (code "76") (name "PCF1_D3") (class "Default")
      (node (ref "JP10") (pin "3") (pinfunction "3_3") (pintype "passive"))
      (node (ref "U3") (pin "7") (pinfunction "P3_7") (pintype "bidirectional"))
    )
    (net (code "77") (name "PCF1_D4") (class "Default")
      (node (ref "JP10") (pin "4") (pinfunction "4_4") (pintype "passive"))
      (node (ref "U3") (pin "9") (pinfunction "P4_9") (pintype "bidirectional"))
    )
    (net (code "78") (name "PCF1_D5") (class "Default")
      (node (ref "JP10") (pin "6") (pinfunction "6_6") (pintype "passive"))
      (node (ref "U3") (pin "10") (pinfunction "P5_10") (pintype "bidirectional"))
    )
    (net (code "79") (name "PCF1_D6") (class "Default")
      (node (ref "JP10") (pin "8") (pinfunction "8_8") (pintype "passive"))
      (node (ref "U3") (pin "11") (pinfunction "P6_11") (pintype "bidirectional"))
    )
    (net (code "80") (name "PCF1_D7") (class "Default")
      (node (ref "JP10") (pin "10") (pinfunction "10_10") (pintype "passive"))
      (node (ref "U3") (pin "12") (pinfunction "P7_12") (pintype "bidirectional"))
    )
    (net (code "81") (name "PCF2_D0") (class "Default")
      (node (ref "JP11") (pin "9") (pinfunction "9_9") (pintype "passive"))
      (node (ref "U4") (pin "4") (pinfunction "P0_4") (pintype "bidirectional"))
    )
    (net (code "82") (name "PCF2_D1") (class "Default")
      (node (ref "JP11") (pin "7") (pinfunction "7_7") (pintype "passive"))
      (node (ref "U4") (pin "5") (pinfunction "P1_5") (pintype "bidirectional"))
    )
    (net (code "83") (name "PCF2_D2") (class "Default")
      (node (ref "JP11") (pin "5") (pinfunction "5_5") (pintype "passive"))
      (node (ref "U4") (pin "6") (pinfunction "P2_6") (pintype "bidirectional"))
    )
    (net (code "84") (name "PCF2_D3") (class "Default")
      (node (ref "JP11") (pin "3") (pinfunction "3_3") (pintype "passive"))
      (node (ref "U4") (pin "7") (pinfunction "P3_7") (pintype "bidirectional"))
    )
    (net (code "85") (name "PCF2_D4") (class "Default")
      (node (ref "JP11") (pin "4") (pinfunction "4_4") (pintype "passive"))
      (node (ref "U4") (pin "9") (pinfunction "P4_9") (pintype "bidirectional"))
    )
    (net (code "86") (name "PCF2_D5") (class "Default")
      (node (ref "JP11") (pin "6") (pinfunction "6_6") (pintype "passive"))
      (node (ref "U4") (pin "10") (pinfunction "P5_10") (pintype "bidirectional"))
    )
    (net (code "87") (name "PCF2_D6") (class "Default")
      (node (ref "JP11") (pin "8") (pinfunction "8_8") (pintype "passive"))
      (node (ref "U4") (pin "11") (pinfunction "P6_11") (pintype "bidirectional"))
    )
    (net (code "88") (name "PCF2_D7") (class "Default")
      (node (ref "JP11") (pin "10") (pinfunction "10_10") (pintype "passive"))
      (node (ref "U4") (pin "12") (pinfunction "P7_12") (pintype "bidirectional"))
    )
    (net (code "89") (name "PCF3_D0") (class "Default")
      (node (ref "JP12") (pin "9") (pinfunction "9_9") (pintype "passive"))
      (node (ref "U5") (pin "4") (pinfunction "P0_4") (pintype "bidirectional"))
    )
    (net (code "90") (name "PCF3_D1") (class "Default")
      (node (ref "JP12") (pin "7") (pinfunction "7_7") (pintype "passive"))
      (node (ref "U5") (pin "5") (pinfunction "P1_5") (pintype "bidirectional"))
    )
    (net (code "91") (name "PCF3_D2") (class "Default")
      (node (ref "JP12") (pin "5") (pinfunction "5_5") (pintype "passive"))
      (node (ref "U5") (pin "6") (pinfunction "P2_6") (pintype "bidirectional"))
    )
    (net (code "92") (name "PCF3_D3") (class "Default")
      (node (ref "JP12") (pin "3") (pinfunction "3_3") (pintype "passive"))
      (node (ref "U5") (pin "7") (pinfunction "P3_7") (pintype "bidirectional"))
    )
    (net (code "93") (name "PCF3_D4") (class "Default")
      (node (ref "JP12") (pin "4") (pinfunction "4_4") (pintype "passive"))
      (node (ref "U5") (pin "9") (pinfunction "P4_9") (pintype "bidirectional"))
    )
    (net (code "94") (name "PCF3_D5") (class "Default")
      (node (ref "JP12") (pin "6") (pinfunction "6_6") (pintype "passive"))
      (node (ref "U5") (pin "10") (pinfunction "P5_10") (pintype "bidirectional"))
    )
    (net (code "95") (name "PCF3_D6") (class "Default")
      (node (ref "JP12") (pin "8") (pinfunction "8_8") (pintype "passive"))
      (node (ref "U5") (pin "11") (pinfunction "P6_11") (pintype "bidirectional"))
    )
    (net (code "96") (name "PCF3_D7") (class "Default")
      (node (ref "JP12") (pin "10") (pinfunction "10_10") (pintype "passive"))
      (node (ref "U5") (pin "12") (pinfunction "P7_12") (pintype "bidirectional"))
    )
    (net (code "97") (name "RI1") (class "Default")
      (node (ref "M1") (pin "48") (pinfunction "P2.6_48") (pintype "bidirectional"))
    )
    (net (code "98") (name "RTS1") (class "Default")
      (node (ref "M1") (pin "49") (pinfunction "P2.7_49") (pintype "bidirectional"))
      (node (ref "U9") (pin "1") (pinfunction "T2IN_1") (pintype "input"))
    )
    (net (code "99") (name "RXD1") (class "Default")
      (node (ref "M1") (pin "43") (pinfunction "P2.1_43") (pintype "bidirectional"))
      (node (ref "U10") (pin "9") (pinfunction "I0_9") (pintype "input"))
      (node (ref "U8") (pin "20") (pinfunction "R2OUT_20") (pintype "output"))
    )
    (net (code "100") (name "RXD3") (class "Default")
      (node (ref "JP13") (pin "2") (pinfunction "2_2") (pintype "passive"))
      (node (ref "M1") (pin "10") (pinfunction "P0.1_10") (pintype "bidirectional"))
      (node (ref "U10") (pin "1") (pinfunction "I0_1") (pintype "input"))
    )
    (net (code "101") (name "SCL0") (class "Default")
      (node (ref "JP4") (pin "2") (pinfunction "2_2") (pintype "passive"))
      (node (ref "M1") (pin "26") (pinfunction "P0.28_26") (pintype "bidirectional"))
      (node (ref "U1") (pin "6") (pinfunction "SCL_6") (pintype "input"))
      (node (ref "U2") (pin "14") (pinfunction "SCL_14") (pintype "input"))
      (node (ref "U3") (pin "14") (pinfunction "SCL_14") (pintype "input"))
      (node (ref "U4") (pin "14") (pinfunction "SCL_14") (pintype "input"))
      (node (ref "U5") (pin "14") (pinfunction "SCL_14") (pintype "input"))
    )
    (net (code "102") (name "SDA0") (class "Default")
      (node (ref "JP4") (pin "1") (pinfunction "1_1") (pintype "passive"))
      (node (ref "M1") (pin "25") (pinfunction "P0.27_25") (pintype "bidirectional"))
      (node (ref "U1") (pin "5") (pinfunction "SDA_5") (pintype "bidirectional"))
      (node (ref "U2") (pin "15") (pinfunction "SDA_15") (pintype "bidirectional"))
      (node (ref "U3") (pin "15") (pinfunction "SDA_15") (pintype "bidirectional"))
      (node (ref "U4") (pin "15") (pinfunction "SDA_15") (pintype "bidirectional"))
      (node (ref "U5") (pin "15") (pinfunction "SDA_15") (pintype "bidirectional"))
    )
    (net (code "103") (name "TXD1") (class "Default")
      (node (ref "M1") (pin "42") (pinfunction "P2.0_42") (pintype "bidirectional"))
      (node (ref "U10") (pin "4") (pinfunction "I0_4") (pintype "input"))
      (node (ref "U8") (pin "1") (pinfunction "T2IN_1") (pintype "input"))
    )
    (net (code "104") (name "TXD3") (class "Default")
      (node (ref "JP13") (pin "1") (pinfunction "1_1") (pintype "passive"))
      (node (ref "M1") (pin "9") (pinfunction "P0.0_9") (pintype "bidirectional"))
      (node (ref "U10") (pin "12") (pinfunction "I0_12") (pintype "input"))
    )
    (net (code "105") (name "USB_DM") (class "Default")
      (node (ref "M1") (pin "36") (pinfunction "USB_DM_36") (pintype "bidirectional"))
      (node (ref "M2") (pin "D-") (pinfunction "D-_D-") (pintype "bidirectional"))
    )
    (net (code "106") (name "USB_DP") (class "Default")
      (node (ref "M1") (pin "37") (pinfunction "USB_DP_37") (pintype "bidirectional"))
      (node (ref "M2") (pin "D+") (pinfunction "D+_D+") (pintype "bidirectional"))
    )
    (net (code "107") (name "unconnected-(JP2-Pad17)") (class "Default")
      (node (ref "JP2") (pin "17") (pinfunction "17_17") (pintype "passive"))
    )
    (net (code "108") (name "unconnected-(M1-3V3-Pad28)") (class "Default")
      (node (ref "M1") (pin "28") (pinfunction "3V3_28") (pintype "bidirectional"))
    )
    (net (code "109") (name "unconnected-(M1-ETH_RDN-Pad32)") (class "Default")
      (node (ref "M1") (pin "32") (pinfunction "ETH_RDN_32") (pintype "bidirectional"))
    )
    (net (code "110") (name "unconnected-(M1-ETH_RDP-Pad33)") (class "Default")
      (node (ref "M1") (pin "33") (pinfunction "ETH_RDP_33") (pintype "bidirectional"))
    )
    (net (code "111") (name "unconnected-(M1-ETH_TDN-Pad34)") (class "Default")
      (node (ref "M1") (pin "34") (pinfunction "ETH_TDN_34") (pintype "bidirectional"))
    )
    (net (code "112") (name "unconnected-(M1-ETH_TDP-Pad35)") (class "Default")
      (node (ref "M1") (pin "35") (pinfunction "ETH_TDP_35") (pintype "bidirectional"))
    )
    (net (code "113") (name "unconnected-(M1-GND2-Pad54)") (class "Default")
      (node (ref "M1") (pin "54") (pinfunction "GND2_54") (pintype "bidirectional"))
    )
    (net (code "114") (name "unconnected-(M1-NC1-Pad29)") (class "Default")
      (node (ref "M1") (pin "29") (pinfunction "NC1_29") (pintype "bidirectional"))
    )
    (net (code "115") (name "unconnected-(M1-NC2-Pad30)") (class "Default")
      (node (ref "M1") (pin "30") (pinfunction "NC2_30") (pintype "bidirectional"))
    )
    (net (code "116") (name "unconnected-(M1-NC3-Pad31)") (class "Default")
      (node (ref "M1") (pin "31") (pinfunction "NC3_31") (pintype "bidirectional"))
    )
    (net (code "117") (name "unconnected-(M1-P0.10-Pad40)") (class "Default")
      (node (ref "M1") (pin "40") (pinfunction "P0.10_40") (pintype "bidirectional"))
    )
    (net (code "118") (name "unconnected-(M1-P0.11-Pad41)") (class "Default")
      (node (ref "M1") (pin "41") (pinfunction "P0.11_41") (pintype "bidirectional"))
    )
    (net (code "119") (name "unconnected-(M1-P0.15-Pad13)") (class "Default")
      (node (ref "M1") (pin "13") (pinfunction "P0.15_13") (pintype "bidirectional"))
    )
    (net (code "120") (name "unconnected-(M1-P1.18-Pad73)") (class "Default")
      (node (ref "M1") (pin "73") (pinfunction "P1.18_73") (pintype "bidirectional"))
    )
    (net (code "121") (name "unconnected-(M1-P1.19-Pad72)") (class "Default")
      (node (ref "M1") (pin "72") (pinfunction "P1.19_72") (pintype "bidirectional"))
    )
    (net (code "122") (name "unconnected-(M1-P1.20-Pad71)") (class "Default")
      (node (ref "M1") (pin "71") (pinfunction "P1.20_71") (pintype "bidirectional"))
    )
    (net (code "123") (name "unconnected-(M1-P1.21-Pad70)") (class "Default")
      (node (ref "M1") (pin "70") (pinfunction "P1.21_70") (pintype "bidirectional"))
    )
    (net (code "124") (name "unconnected-(M1-P1.22-Pad69)") (class "Default")
      (node (ref "M1") (pin "69") (pinfunction "P1.22_69") (pintype "bidirectional"))
    )
    (net (code "125") (name "unconnected-(M1-P1.23-Pad68)") (class "Default")
      (node (ref "M1") (pin "68") (pinfunction "P1.23_68") (pintype "bidirectional"))
    )
    (net (code "126") (name "unconnected-(M1-P1.24-Pad67)") (class "Default")
      (node (ref "M1") (pin "67") (pinfunction "P1.24_67") (pintype "bidirectional"))
    )
    (net (code "127") (name "unconnected-(M1-P1.25-Pad66)") (class "Default")
      (node (ref "M1") (pin "66") (pinfunction "P1.25_66") (pintype "bidirectional"))
    )
    (net (code "128") (name "unconnected-(M1-P1.26-Pad65)") (class "Default")
      (node (ref "M1") (pin "65") (pinfunction "P1.26_65") (pintype "bidirectional"))
    )
    (net (code "129") (name "unconnected-(M1-P1.27-Pad64)") (class "Default")
      (node (ref "M1") (pin "64") (pinfunction "P1.27_64") (pintype "bidirectional"))
    )
    (net (code "130") (name "unconnected-(M1-P1.28-Pad63)") (class "Default")
      (node (ref "M1") (pin "63") (pinfunction "P1.28_63") (pintype "bidirectional"))
    )
    (net (code "131") (name "unconnected-(M1-P1.29-Pad62)") (class "Default")
      (node (ref "M1") (pin "62") (pinfunction "P1.29_62") (pintype "bidirectional"))
    )
    (net (code "132") (name "unconnected-(M1-P1.30-Pad19)") (class "Default")
      (node (ref "M1") (pin "19") (pinfunction "P1.30_19") (pintype "bidirectional"))
    )
    (net (code "133") (name "unconnected-(M1-P1.31-Pad20)") (class "Default")
      (node (ref "M1") (pin "20") (pinfunction "P1.31_20") (pintype "bidirectional"))
    )
    (net (code "134") (name "unconnected-(M1-P2.8-Pad50)") (class "Default")
      (node (ref "M1") (pin "50") (pinfunction "P2.8_50") (pintype "bidirectional"))
    )
    (net (code "135") (name "unconnected-(M1-P2.9-Pad55)") (class "Default")
      (node (ref "M1") (pin "55") (pinfunction "P2.9_55") (pintype "bidirectional"))
    )
    (net (code "136") (name "unconnected-(M1-P2.11-Pad52)") (class "Default")
      (node (ref "M1") (pin "52") (pinfunction "P2.11_52") (pintype "bidirectional"))
    )
    (net (code "137") (name "unconnected-(M1-P2.12-Pad53)") (class "Default")
      (node (ref "M1") (pin "53") (pinfunction "P2.12_53") (pintype "bidirectional"))
    )
    (net (code "138") (name "unconnected-(M1-P2.13-Pad27)") (class "Default")
      (node (ref "M1") (pin "27") (pinfunction "P2.13_27") (pintype "bidirectional"))
    )
    (net (code "139") (name "unconnected-(M1-P3.25-Pad61)") (class "Default")
      (node (ref "M1") (pin "61") (pinfunction "P3.25_61") (pintype "bidirectional"))
    )
    (net (code "140") (name "unconnected-(M1-P3.26-Pad60)") (class "Default")
      (node (ref "M1") (pin "60") (pinfunction "P3.26_60") (pintype "bidirectional"))
    )
    (net (code "141") (name "unconnected-(M1-P4.28-Pad59)") (class "Default")
      (node (ref "M1") (pin "59") (pinfunction "P4.28_59") (pintype "bidirectional"))
    )
    (net (code "142") (name "unconnected-(M1-P4.29-Pad58)") (class "Default")
      (node (ref "M1") (pin "58") (pinfunction "P4.29_58") (pintype "bidirectional"))
    )
    (net (code "143") (name "unconnected-(M1-RESET-Pad4)") (class "Default")
      (node (ref "M1") (pin "4") (pinfunction "RESET_4") (pintype "bidirectional"))
    )
    (net (code "144") (name "unconnected-(M1-VBAT-Pad3)") (class "Default")
      (node (ref "M1") (pin "3") (pinfunction "VBAT_3") (pintype "bidirectional"))
    )
    (net (code "145") (name "unconnected-(M2-PadID)") (class "Default")
      (node (ref "M2") (pin "ID") (pinfunction "ID_ID") (pintype "bidirectional"))
    )
    (net (code "146") (name "unconnected-(M3-Pad1)") (class "Default")
      (node (ref "M3") (pin "1") (pinfunction "1_1") (pintype "passive"))
    )
    (net (code "147") (name "unconnected-(M3-Pad9)") (class "Default")
      (node (ref "M3") (pin "9") (pinfunction "9_9") (pintype "passive"))
    )
    (net (code "148") (name "unconnected-(U8-R1IN-Pad4)") (class "Default")
      (node (ref "U8") (pin "4") (pinfunction "R1IN_4") (pintype "input"))
    )
    (net (code "149") (name "unconnected-(U8-R1OUT-Pad3)") (class "Default")
      (node (ref "U8") (pin "3") (pinfunction "R1OUT_3") (pintype "output"))
    )
    (net (code "150") (name "unconnected-(U8-T1IN-Pad2)") (class "Default")
      (node (ref "U8") (pin "2") (pinfunction "T1IN_2") (pintype "input"))
    )
    (net (code "151") (name "unconnected-(U8-T1OUT-Pad5)") (class "Default")
      (node (ref "U8") (pin "5") (pinfunction "T1OUT_5") (pintype "output"))
    )
  )
)
